# RotaryController.net
KiCad netlist of a schematic drawn in EAGLE
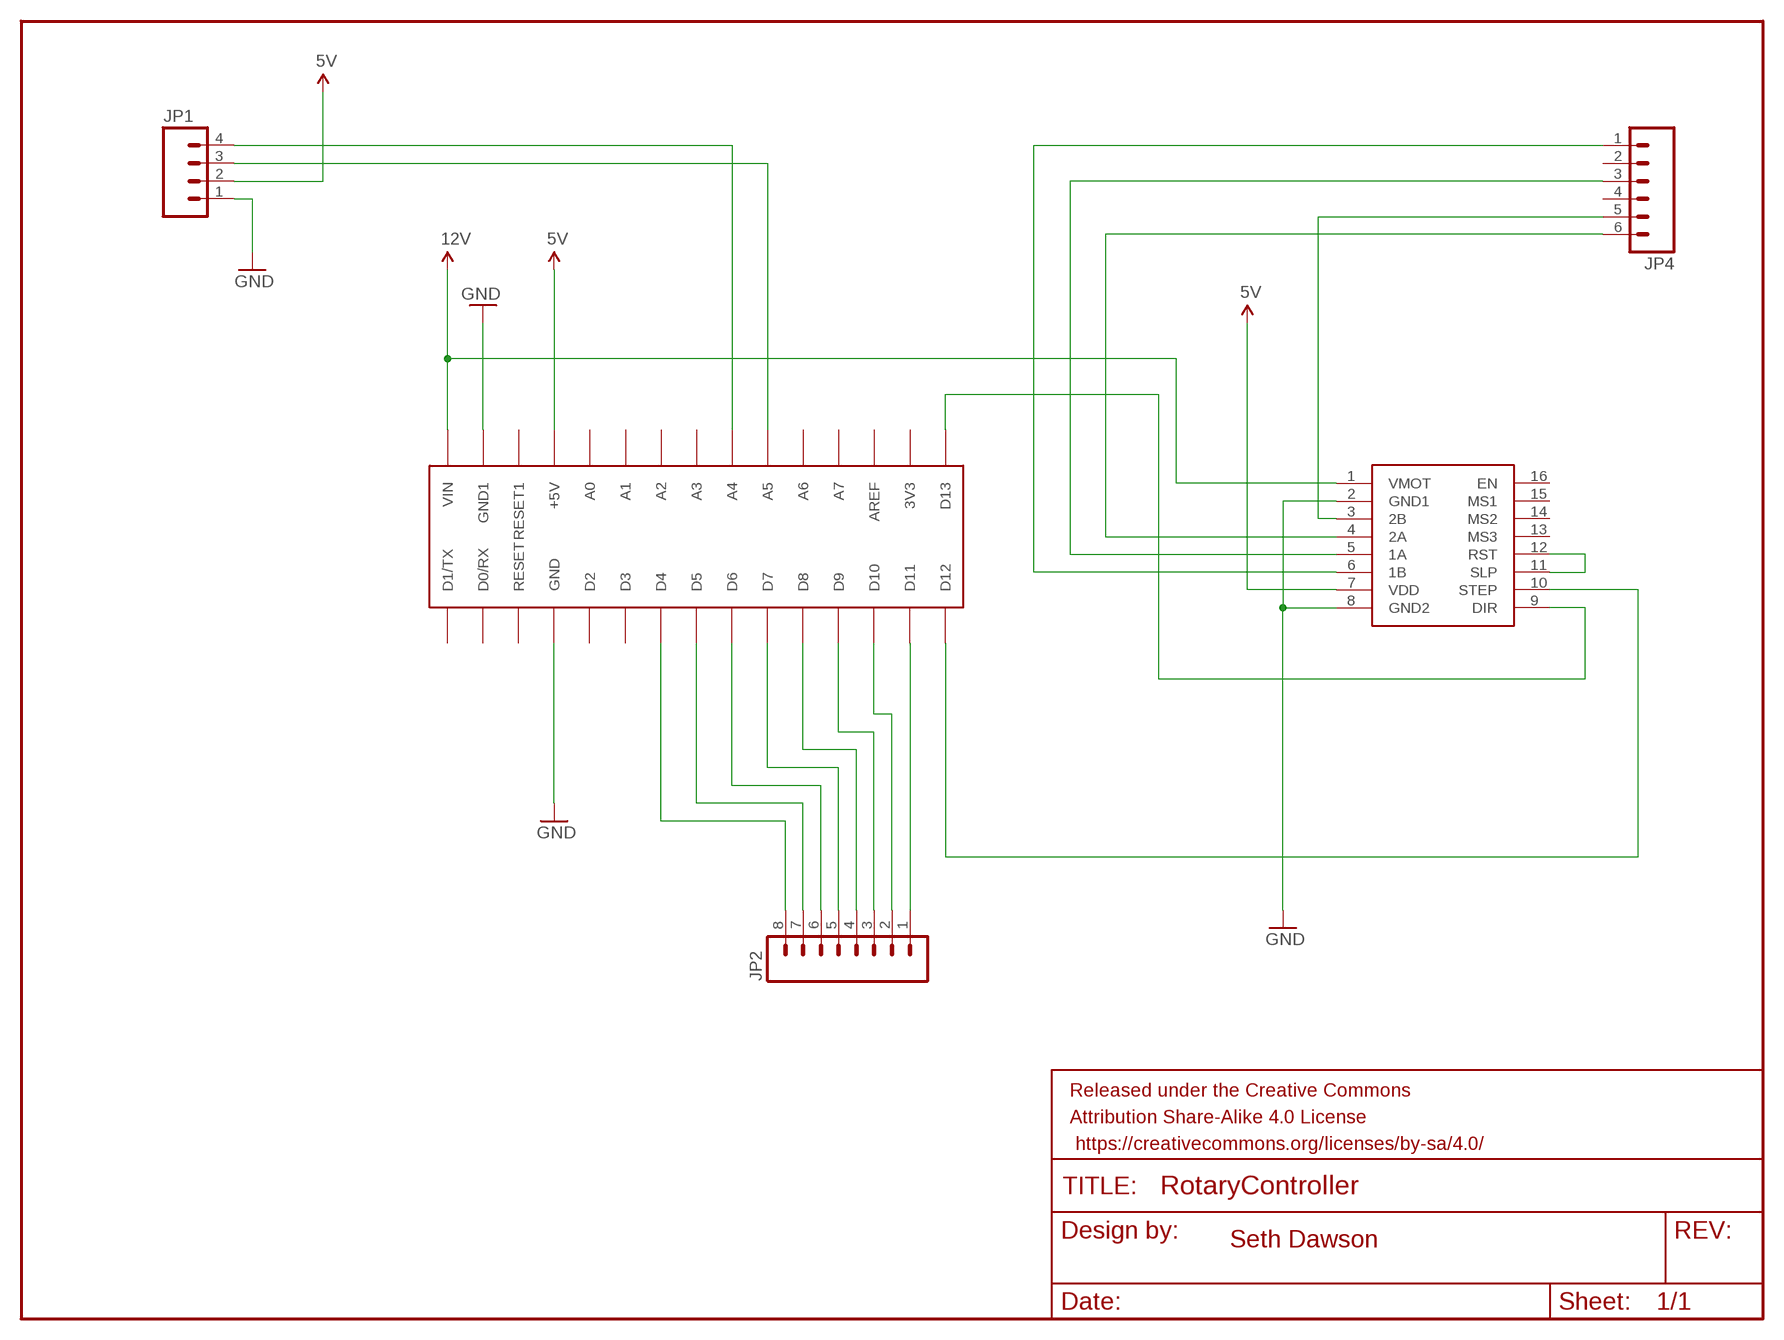
[diagram p0: schematic, sheet 1]

(export (version "E")
  (design (tool "Eeschema 10.0.6"))
  (components
    (comp (ref "FRAME1")
      (value "FRAME-LETTER")
      (footprint "eagle-import:CREATIVE_COMMONS")
      (libsource (lib "eagle-import") (part "FRAME-LETTER"))
    )
    (comp (ref "JP1")
      (value "M04LOCK")
      (footprint "eagle-import:1X04_LOCK")
      (libsource (lib "eagle-import") (part "M04LOCK"))
    )
    (comp (ref "JP2")
      (value "M08")
      (footprint "eagle-import:1X08_ROUND")
      (libsource (lib "eagle-import") (part "M08"))
    )
    (comp (ref "JP4")
      (value "M06LOCK")
      (footprint "eagle-import:1X06_LOCK")
      (libsource (lib "eagle-import") (part "M06LOCK"))
    )
    (comp (ref "U$1")
      (value "ARDUINONANO")
      (footprint "eagle-import:PDIP-32")
      (libsource (lib "eagle-import") (part "ARDUINONANO"))
    )
    (comp (ref "U$2")
      (value "POLOLUESTEPPERDRIVER")
      (footprint "eagle-import:DIL16")
      (libsource (lib "eagle-import") (part "POLOLUESTEPPERDRIVER"))
    )
  )
  (nets
    (net (code "1") (name "5V") (class "Default")
      (node (ref "JP1") (pin "2") (pinfunction "2_2") (pintype "passive"))
      (node (ref "U$1") (pin "+5V") (pinfunction "+5V_+5V") (pintype "bidirectional"))
      (node (ref "U$2") (pin "7") (pinfunction "VDD_7") (pintype "power_in"))
    )
    (net (code "2") (name "12V") (class "Default")
      (node (ref "U$1") (pin "VIN") (pinfunction "VIN_VIN") (pintype "bidirectional"))
      (node (ref "U$2") (pin "1") (pinfunction "VMOT_1") (pintype "power_in"))
    )
    (net (code "3") (name "GND") (class "Default")
      (node (ref "JP1") (pin "1") (pinfunction "1_1") (pintype "passive"))
      (node (ref "U$1") (pin "GND") (pinfunction "GND_GND") (pintype "bidirectional"))
      (node (ref "U$1") (pin "GND1") (pinfunction "GND1_GND1") (pintype "bidirectional"))
      (node (ref "U$2") (pin "2") (pinfunction "GND1_2") (pintype "power_in"))
      (node (ref "U$2") (pin "8") (pinfunction "GND2_8") (pintype "power_in"))
    )
    (net (code "4") (name "Net-(JP1-Pad3)") (class "Default")
      (node (ref "JP1") (pin "3") (pinfunction "3_3") (pintype "passive"))
      (node (ref "U$1") (pin "A5") (pinfunction "A5_A5") (pintype "bidirectional"))
    )
    (net (code "5") (name "Net-(JP1-Pad4)") (class "Default")
      (node (ref "JP1") (pin "4") (pinfunction "4_4") (pintype "passive"))
      (node (ref "U$1") (pin "A4") (pinfunction "A4_A4") (pintype "bidirectional"))
    )
    (net (code "6") (name "Net-(JP2-Pad1)") (class "Default")
      (node (ref "JP2") (pin "1") (pinfunction "1_1") (pintype "passive"))
      (node (ref "U$1") (pin "D11") (pinfunction "D11_D11") (pintype "bidirectional"))
    )
    (net (code "7") (name "Net-(JP2-Pad2)") (class "Default")
      (node (ref "JP2") (pin "2") (pinfunction "2_2") (pintype "passive"))
      (node (ref "U$1") (pin "D10") (pinfunction "D10_D10") (pintype "bidirectional"))
    )
    (net (code "8") (name "Net-(JP2-Pad3)") (class "Default")
      (node (ref "JP2") (pin "3") (pinfunction "3_3") (pintype "passive"))
      (node (ref "U$1") (pin "D9") (pinfunction "D9_D9") (pintype "bidirectional"))
    )
    (net (code "9") (name "Net-(JP2-Pad4)") (class "Default")
      (node (ref "JP2") (pin "4") (pinfunction "4_4") (pintype "passive"))
      (node (ref "U$1") (pin "D8") (pinfunction "D8_D8") (pintype "bidirectional"))
    )
    (net (code "10") (name "Net-(JP2-Pad5)") (class "Default")
      (node (ref "JP2") (pin "5") (pinfunction "5_5") (pintype "passive"))
      (node (ref "U$1") (pin "D7") (pinfunction "D7_D7") (pintype "bidirectional"))
    )
    (net (code "11") (name "Net-(JP2-Pad6)") (class "Default")
      (node (ref "JP2") (pin "6") (pinfunction "6_6") (pintype "passive"))
      (node (ref "U$1") (pin "D6") (pinfunction "D6_D6") (pintype "bidirectional"))
    )
    (net (code "12") (name "Net-(JP2-Pad7)") (class "Default")
      (node (ref "JP2") (pin "7") (pinfunction "7_7") (pintype "passive"))
      (node (ref "U$1") (pin "D5") (pinfunction "D5_D5") (pintype "bidirectional"))
    )
    (net (code "13") (name "Net-(JP2-Pad8)") (class "Default")
      (node (ref "JP2") (pin "8") (pinfunction "8_8") (pintype "passive"))
      (node (ref "U$1") (pin "D4") (pinfunction "D4_D4") (pintype "bidirectional"))
    )
    (net (code "14") (name "Net-(U$2-1A)") (class "Default")
      (node (ref "JP4") (pin "3") (pinfunction "3_3") (pintype "passive"))
      (node (ref "U$2") (pin "5") (pinfunction "1A_5") (pintype "output"))
    )
    (net (code "15") (name "Net-(U$2-1B)") (class "Default")
      (node (ref "JP4") (pin "1") (pinfunction "1_1") (pintype "passive"))
      (node (ref "U$2") (pin "6") (pinfunction "1B_6") (pintype "output"))
    )
    (net (code "16") (name "Net-(U$2-2A)") (class "Default")
      (node (ref "JP4") (pin "6") (pinfunction "6_6") (pintype "passive"))
      (node (ref "U$2") (pin "4") (pinfunction "2A_4") (pintype "output"))
    )
    (net (code "17") (name "Net-(U$2-2B)") (class "Default")
      (node (ref "JP4") (pin "5") (pinfunction "5_5") (pintype "passive"))
      (node (ref "U$2") (pin "3") (pinfunction "2B_3") (pintype "output"))
    )
    (net (code "18") (name "Net-(U$2-DIR)") (class "Default")
      (node (ref "U$1") (pin "D13") (pinfunction "D13_D13") (pintype "bidirectional"))
      (node (ref "U$2") (pin "9") (pinfunction "DIR_9") (pintype "input"))
    )
    (net (code "19") (name "Net-(U$2-RST)") (class "Default")
      (node (ref "U$2") (pin "11") (pinfunction "SLP_11") (pintype "input"))
      (node (ref "U$2") (pin "12") (pinfunction "RST_12") (pintype "input"))
    )
    (net (code "20") (name "Net-(U$2-STEP)") (class "Default")
      (node (ref "U$1") (pin "D12") (pinfunction "D12_D12") (pintype "bidirectional"))
      (node (ref "U$2") (pin "10") (pinfunction "STEP_10") (pintype "input"))
    )
    (net (code "21") (name "unconnected-(JP4-Pad2)") (class "Default")
      (node (ref "JP4") (pin "2") (pinfunction "2_2") (pintype "passive"))
    )
    (net (code "22") (name "unconnected-(JP4-Pad4)") (class "Default")
      (node (ref "JP4") (pin "4") (pinfunction "4_4") (pintype "passive"))
    )
    (net (code "23") (name "unconnected-(U$1-Pad3V3)") (class "Default")
      (node (ref "U$1") (pin "3V3") (pinfunction "3V3_3V3") (pintype "bidirectional"))
    )
    (net (code "24") (name "unconnected-(U$1-PadA0)") (class "Default")
      (node (ref "U$1") (pin "A0") (pinfunction "A0_A0") (pintype "bidirectional"))
    )
    (net (code "25") (name "unconnected-(U$1-PadA1)") (class "Default")
      (node (ref "U$1") (pin "A1") (pinfunction "A1_A1") (pintype "bidirectional"))
    )
    (net (code "26") (name "unconnected-(U$1-PadA2)") (class "Default")
      (node (ref "U$1") (pin "A2") (pinfunction "A2_A2") (pintype "bidirectional"))
    )
    (net (code "27") (name "unconnected-(U$1-PadA3)") (class "Default")
      (node (ref "U$1") (pin "A3") (pinfunction "A3_A3") (pintype "bidirectional"))
    )
    (net (code "28") (name "unconnected-(U$1-PadA6)") (class "Default")
      (node (ref "U$1") (pin "A6") (pinfunction "A6_A6") (pintype "bidirectional"))
    )
    (net (code "29") (name "unconnected-(U$1-PadA7)") (class "Default")
      (node (ref "U$1") (pin "A7") (pinfunction "A7_A7") (pintype "bidirectional"))
    )
    (net (code "30") (name "unconnected-(U$1-PadAREF)") (class "Default")
      (node (ref "U$1") (pin "AREF") (pinfunction "AREF_AREF") (pintype "bidirectional"))
    )
    (net (code "31") (name "unconnected-(U$1-PadD0{slash}RX)") (class "Default")
      (node (ref "U$1") (pin "D0/RX") (pinfunction "D0/RX_D0/RX") (pintype "bidirectional"))
    )
    (net (code "32") (name "unconnected-(U$1-PadD1{slash}TX)") (class "Default")
      (node (ref "U$1") (pin "D1/TX") (pinfunction "D1/TX_D1/TX") (pintype "bidirectional"))
    )
    (net (code "33") (name "unconnected-(U$1-PadD2)") (class "Default")
      (node (ref "U$1") (pin "D2") (pinfunction "D2_D2") (pintype "bidirectional"))
    )
    (net (code "34") (name "unconnected-(U$1-PadD3)") (class "Default")
      (node (ref "U$1") (pin "D3") (pinfunction "D3_D3") (pintype "bidirectional"))
    )
    (net (code "35") (name "unconnected-(U$1-PadRESET)") (class "Default")
      (node (ref "U$1") (pin "RESET") (pinfunction "RESET_RESET") (pintype "bidirectional"))
    )
    (net (code "36") (name "unconnected-(U$1-PadRESET1)") (class "Default")
      (node (ref "U$1") (pin "RESET1") (pinfunction "RESET1_RESET1") (pintype "bidirectional"))
    )
    (net (code "37") (name "unconnected-(U$2-EN-Pad16)") (class "Default")
      (node (ref "U$2") (pin "16") (pinfunction "EN_16") (pintype "input"))
    )
    (net (code "38") (name "unconnected-(U$2-MS1-Pad15)") (class "Default")
      (node (ref "U$2") (pin "15") (pinfunction "MS1_15") (pintype "input"))
    )
    (net (code "39") (name "unconnected-(U$2-MS2-Pad14)") (class "Default")
      (node (ref "U$2") (pin "14") (pinfunction "MS2_14") (pintype "input"))
    )
    (net (code "40") (name "unconnected-(U$2-MS3-Pad13)") (class "Default")
      (node (ref "U$2") (pin "13") (pinfunction "MS3_13") (pintype "input"))
    )
  )
)
